# ClosedLoop_Drive_PowerSupply.net
KiCad netlist of a schematic drawn in Altium Designer
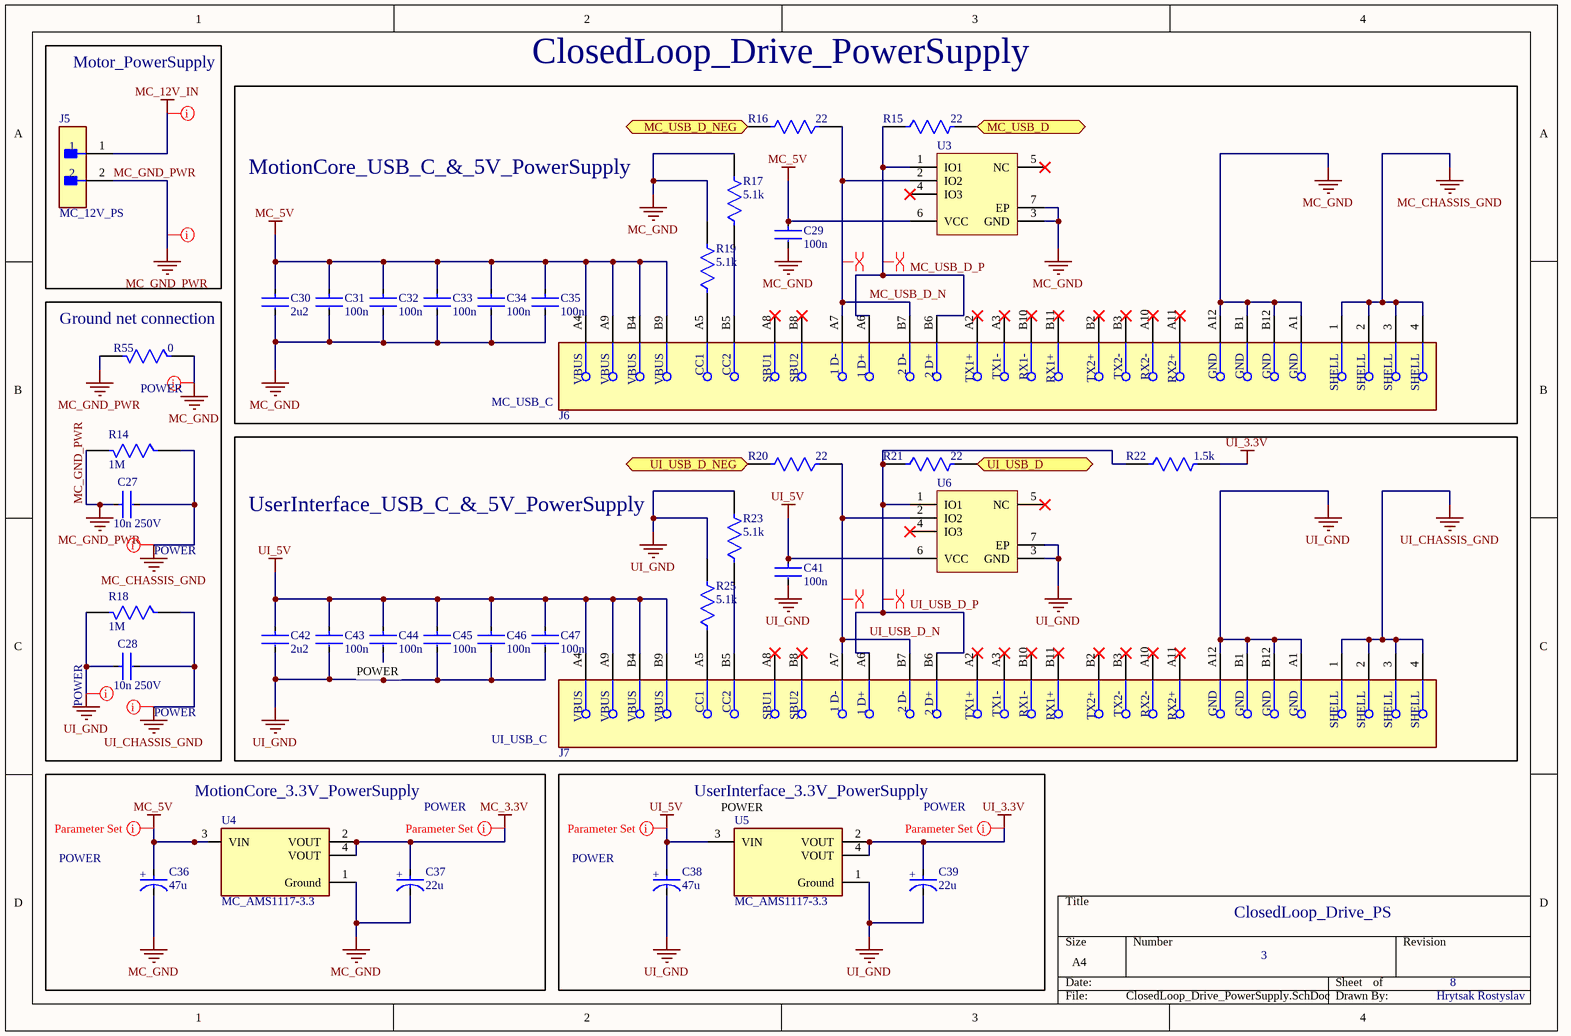
[diagram p0: ClosedLoop_Drive_PowerSupply.SchDoc]

(export (version "E")
  (design (tool "Eeschema 10.0.6"))
  (components
    (comp (ref "C27")
      (value "10n 250V")
      (footprint "FP-0805-L_2_01_0_2-W_1_25-MFG")
      (description "0805")
      (fields (field (name "TOLERANCE") "10%"))
      (libsource (lib "Altium Content Vault") (part "b4654b650e69147ec39a6b967a45e02"))
    )
    (comp (ref "C28")
      (value "10n 250V")
      (footprint "FP-0805-L_2_01_0_2-W_1_25-MFG")
      (description "0805")
      (fields (field (name "TOLERANCE") "10%"))
      (libsource (lib "Altium Content Vault") (part "b4654b650e69147ec39a6b967a45e02"))
    )
    (comp (ref "C29")
      (value "100n")
      (footprint "FP-0805-L_2_01_0_2-W_1_25-MFG")
      (description "0805")
      (fields (field (name "TOLERANCE") "10%"))
      (libsource (lib "Altium Content Vault") (part "b4654b650e69147ec39a6b967a45e02"))
    )
    (comp (ref "C30")
      (value "2u2")
      (footprint "FP-0805-L_2_01_0_2-W_1_25-MFG")
      (description "0805")
      (fields (field (name "TOLERANCE") "10%"))
      (libsource (lib "Altium Content Vault") (part "b4654b650e69147ec39a6b967a45e02"))
    )
    (comp (ref "C31")
      (value "100n")
      (footprint "FP-0805-L_2_01_0_2-W_1_25-MFG")
      (description "0805")
      (fields (field (name "TOLERANCE") "10%"))
      (libsource (lib "Altium Content Vault") (part "b4654b650e69147ec39a6b967a45e02"))
    )
    (comp (ref "C32")
      (value "100n")
      (footprint "FP-0805-L_2_01_0_2-W_1_25-MFG")
      (description "0805")
      (fields (field (name "TOLERANCE") "10%"))
      (libsource (lib "Altium Content Vault") (part "b4654b650e69147ec39a6b967a45e02"))
    )
    (comp (ref "C33")
      (value "100n")
      (footprint "FP-0805-L_2_01_0_2-W_1_25-MFG")
      (description "0805")
      (fields (field (name "TOLERANCE") "10%"))
      (libsource (lib "Altium Content Vault") (part "b4654b650e69147ec39a6b967a45e02"))
    )
    (comp (ref "C34")
      (value "100n")
      (footprint "FP-0805-L_2_01_0_2-W_1_25-MFG")
      (description "0805")
      (fields (field (name "TOLERANCE") "10%"))
      (libsource (lib "Altium Content Vault") (part "b4654b650e69147ec39a6b967a45e02"))
    )
    (comp (ref "C35")
      (value "100n")
      (footprint "FP-0805-L_2_01_0_2-W_1_25-MFG")
      (description "0805")
      (fields (field (name "TOLERANCE") "10%"))
      (libsource (lib "Altium Content Vault") (part "b4654b650e69147ec39a6b967a45e02"))
    )
    (comp (ref "C36")
      (value "47u")
      (footprint "FP-RAD-TH-D_6_3_0_5-L_11-MFG")
      (description "Aluminum Electrolytic Capacitors (Radial Lead Type) AEC-Q200 Qualified 100uF ±20% 25V")
      (fields (field (name "TOLERANCE") "20%"))
      (libsource (lib "Altium Content Vault") (part "203bc49f2ac43e59fd269a8c329ed05"))
    )
    (comp (ref "C37")
      (value "22u")
      (footprint "FP-RAD-TH-D_6_3_0_5-L_11-MFG")
      (description "Aluminum Electrolytic Capacitors (Radial Lead Type) AEC-Q200 Qualified 100uF ±20% 25V")
      (fields (field (name "TOLERANCE") "20%"))
      (libsource (lib "Altium Content Vault") (part "203bc49f2ac43e59fd269a8c329ed05"))
    )
    (comp (ref "C38")
      (value "47u")
      (footprint "FP-RAD-TH-D_6_3_0_5-L_11-MFG")
      (description "Aluminum Electrolytic Capacitors (Radial Lead Type) AEC-Q200 Qualified 100uF ±20% 25V")
      (fields (field (name "TOLERANCE") "20%"))
      (libsource (lib "Altium Content Vault") (part "203bc49f2ac43e59fd269a8c329ed05"))
    )
    (comp (ref "C39")
      (value "22u")
      (footprint "FP-RAD-TH-D_6_3_0_5-L_11-MFG")
      (description "Aluminum Electrolytic Capacitors (Radial Lead Type) AEC-Q200 Qualified 100uF ±20% 25V")
      (fields (field (name "TOLERANCE") "20%"))
      (libsource (lib "Altium Content Vault") (part "203bc49f2ac43e59fd269a8c329ed05"))
    )
    (comp (ref "C41")
      (value "100n")
      (footprint "FP-0805-L_2_01_0_2-W_1_25-MFG")
      (description "0805")
      (fields (field (name "TOLERANCE") "10%"))
      (libsource (lib "Altium Content Vault") (part "b4654b650e69147ec39a6b967a45e02"))
    )
    (comp (ref "C42")
      (value "2u2")
      (footprint "FP-0805-L_2_01_0_2-W_1_25-MFG")
      (description "0805")
      (fields (field (name "TOLERANCE") "10%"))
      (libsource (lib "Altium Content Vault") (part "b4654b650e69147ec39a6b967a45e02"))
    )
    (comp (ref "C43")
      (value "100n")
      (footprint "FP-0805-L_2_01_0_2-W_1_25-MFG")
      (description "0805")
      (fields (field (name "TOLERANCE") "10%"))
      (libsource (lib "Altium Content Vault") (part "b4654b650e69147ec39a6b967a45e02"))
    )
    (comp (ref "C44")
      (value "100n")
      (footprint "FP-0805-L_2_01_0_2-W_1_25-MFG")
      (description "0805")
      (fields (field (name "TOLERANCE") "10%"))
      (libsource (lib "Altium Content Vault") (part "b4654b650e69147ec39a6b967a45e02"))
    )
    (comp (ref "C45")
      (value "100n")
      (footprint "FP-0805-L_2_01_0_2-W_1_25-MFG")
      (description "0805")
      (fields (field (name "TOLERANCE") "10%"))
      (libsource (lib "Altium Content Vault") (part "b4654b650e69147ec39a6b967a45e02"))
    )
    (comp (ref "C46")
      (value "100n")
      (footprint "FP-0805-L_2_01_0_2-W_1_25-MFG")
      (description "0805")
      (fields (field (name "TOLERANCE") "10%"))
      (libsource (lib "Altium Content Vault") (part "b4654b650e69147ec39a6b967a45e02"))
    )
    (comp (ref "C47")
      (value "100n")
      (footprint "FP-0805-L_2_01_0_2-W_1_25-MFG")
      (description "0805")
      (fields (field (name "TOLERANCE") "10%"))
      (libsource (lib "Altium Content Vault") (part "b4654b650e69147ec39a6b967a45e02"))
    )
    (comp (ref "J5")
      (value "MC_12V_PS")
      (footprint "FP-TSW-102-07-F-S-MFG")
      (description "CONN HEADER VERT 2POS 2.54MM")
      (libsource (lib "Altium Content Vault") (part "3bc925449376181038e59eaffc5286c"))
    )
    (comp (ref "J6")
      (value "MC_USB_C")
      (footprint "FP-12401832E402A-MFG")
      (description "CONN RCP USB3.1 TYPEC 24P SMD RA")
      (libsource (lib "Altium Content Vault") (part "50854493bfec571c3c083d899a0df29"))
    )
    (comp (ref "J7")
      (value "UI_USB_C")
      (footprint "FP-12401832E402A-MFG")
      (description "CONN RCP USB3.1 TYPEC 24P SMD RA")
      (libsource (lib "Altium Content Vault") (part "50854493bfec571c3c083d899a0df29"))
    )
    (comp (ref "R14")
      (value "1M")
      (footprint "FP-MCU0805-IPC_A")
      (description "0805")
      (fields (field (name "TOLERANCE") "0.5%"))
      (libsource (lib "Altium Content Vault") (part "1029c3af85768c4190bb7ad29bc67b5"))
    )
    (comp (ref "R15")
      (value "22")
      (footprint "FP-MCU0805-IPC_A")
      (description "0805")
      (fields (field (name "TOLERANCE") "0.5%"))
      (libsource (lib "Altium Content Vault") (part "1029c3af85768c4190bb7ad29bc67b5"))
    )
    (comp (ref "R16")
      (value "22")
      (footprint "FP-MCU0805-IPC_A")
      (description "0805")
      (fields (field (name "TOLERANCE") "0.5%"))
      (libsource (lib "Altium Content Vault") (part "1029c3af85768c4190bb7ad29bc67b5"))
    )
    (comp (ref "R17")
      (value "5.1k")
      (footprint "FP-MCU0805-IPC_A")
      (description "0805")
      (fields (field (name "TOLERANCE") "0.5%"))
      (libsource (lib "Altium Content Vault") (part "1029c3af85768c4190bb7ad29bc67b5"))
    )
    (comp (ref "R18")
      (value "1M")
      (footprint "FP-MCU0805-IPC_A")
      (description "0805")
      (fields (field (name "TOLERANCE") "0.5%"))
      (libsource (lib "Altium Content Vault") (part "1029c3af85768c4190bb7ad29bc67b5"))
    )
    (comp (ref "R19")
      (value "5.1k")
      (footprint "FP-MCU0805-IPC_A")
      (description "0805")
      (fields (field (name "TOLERANCE") "0.5%"))
      (libsource (lib "Altium Content Vault") (part "1029c3af85768c4190bb7ad29bc67b5"))
    )
    (comp (ref "R20")
      (value "22")
      (footprint "FP-MCU0805-IPC_A")
      (description "0805")
      (fields (field (name "TOLERANCE") "0.5%"))
      (libsource (lib "Altium Content Vault") (part "1029c3af85768c4190bb7ad29bc67b5"))
    )
    (comp (ref "R21")
      (value "22")
      (footprint "FP-MCU0805-IPC_A")
      (description "0805")
      (fields (field (name "TOLERANCE") "0.5%"))
      (libsource (lib "Altium Content Vault") (part "1029c3af85768c4190bb7ad29bc67b5"))
    )
    (comp (ref "R22")
      (value "1.5k")
      (footprint "FP-MCU0805-IPC_A")
      (description "0805")
      (fields (field (name "TOLERANCE") "0.5%"))
      (libsource (lib "Altium Content Vault") (part "1029c3af85768c4190bb7ad29bc67b5"))
    )
    (comp (ref "R23")
      (value "5.1k")
      (footprint "FP-MCU0805-IPC_A")
      (description "0805")
      (fields (field (name "TOLERANCE") "0.5%"))
      (libsource (lib "Altium Content Vault") (part "1029c3af85768c4190bb7ad29bc67b5"))
    )
    (comp (ref "R25")
      (value "5.1k")
      (footprint "FP-MCU0805-IPC_A")
      (description "0805")
      (fields (field (name "TOLERANCE") "0.5%"))
      (libsource (lib "Altium Content Vault") (part "1029c3af85768c4190bb7ad29bc67b5"))
    )
    (comp (ref "R55")
      (value "0")
      (footprint "FP-MCU0805-IPC_A")
      (description "0805")
      (fields (field (name "TOLERANCE") "0.5%"))
      (libsource (lib "Altium Content Vault") (part "1029c3af85768c4190bb7ad29bc67b5"))
    )
    (comp (ref "U3")
      (value "~")
      (footprint "DRS0006A_V")
      (fields (field (name "MANUFACTURER") "Texas Instruments") (field (name "PARTNUMBER") "TPD3E001DRSR"))
      (libsource (lib "Altium Content Vault") (part "TI-TPD3E001-SON_DRS-6"))
    )
    (comp (ref "U4")
      (value "MC_AMS1117-3.3")
      (footprint "FP-AMS1117-IPC_C")
      (description "LDO Voltage Regulators 1A, 3.3V")
      (fields
        (field (name "MANUFACTURER PART NUMBER") "AMS1117-3.3")
        (field (name "OCTOPART") "https://octopart.com/ams1117-3.3-advanced+monolithic+systems-25899300")
      )
      (libsource (lib "Altium Content Vault") (part "8bdbb5f8e77002000e30dd2845d0354"))
    )
    (comp (ref "U5")
      (value "MC_AMS1117-3.3")
      (footprint "FP-AMS1117-IPC_C")
      (description "LDO Voltage Regulators 1A, 3.3V")
      (fields
        (field (name "MANUFACTURER PART NUMBER") "AMS1117-3.3")
        (field (name "OCTOPART") "https://octopart.com/ams1117-3.3-advanced+monolithic+systems-25899300")
      )
      (libsource (lib "Altium Content Vault") (part "8bdbb5f8e77002000e30dd2845d0354"))
    )
    (comp (ref "U6")
      (value "~")
      (footprint "DRS0006A_V")
      (fields (field (name "MANUFACTURER") "Texas Instruments") (field (name "PARTNUMBER") "TPD3E001DRSR"))
      (libsource (lib "Altium Content Vault") (part "TI-TPD3E001-SON_DRS-6"))
    )
  )
  (nets
    (net (code "1") (name "/MC_USB_D") (class "Default")
      (node (ref "R15") (pin "2") (pinfunction "2_2") (pintype "passive"))
    )
    (net (code "2") (name "/MC_USB_D_N") (class "Default")
      (node (ref "J6") (pin "A7") (pinfunction "1_D-_A7") (pintype "passive"))
      (node (ref "J6") (pin "B7") (pinfunction "2_D-_B7") (pintype "passive"))
      (node (ref "R16") (pin "1") (pinfunction "1_1") (pintype "passive"))
      (node (ref "U3") (pin "2") (pinfunction "IO2_2") (pintype "passive"))
    )
    (net (code "3") (name "/MC_USB_D_NEG") (class "Default")
      (node (ref "R16") (pin "2") (pinfunction "2_2") (pintype "passive"))
    )
    (net (code "4") (name "/MC_USB_D_P") (class "Default")
      (node (ref "J6") (pin "A6") (pinfunction "1_D+_A6") (pintype "passive"))
      (node (ref "J6") (pin "B6") (pinfunction "2_D+_B6") (pintype "passive"))
      (node (ref "R15") (pin "1") (pinfunction "1_1") (pintype "passive"))
      (node (ref "U3") (pin "1") (pinfunction "IO1_1") (pintype "passive"))
    )
    (net (code "5") (name "/UI_USB_D") (class "Default")
      (node (ref "R21") (pin "2") (pinfunction "2_2") (pintype "passive"))
    )
    (net (code "6") (name "/UI_USB_D_N") (class "Default")
      (node (ref "J7") (pin "A7") (pinfunction "1_D-_A7") (pintype "passive"))
      (node (ref "J7") (pin "B7") (pinfunction "2_D-_B7") (pintype "passive"))
      (node (ref "R20") (pin "1") (pinfunction "1_1") (pintype "passive"))
      (node (ref "U6") (pin "2") (pinfunction "IO2_2") (pintype "passive"))
    )
    (net (code "7") (name "/UI_USB_D_NEG") (class "Default")
      (node (ref "R20") (pin "2") (pinfunction "2_2") (pintype "passive"))
    )
    (net (code "8") (name "/UI_USB_D_P") (class "Default")
      (node (ref "J7") (pin "A6") (pinfunction "1_D+_A6") (pintype "passive"))
      (node (ref "J7") (pin "B6") (pinfunction "2_D+_B6") (pintype "passive"))
      (node (ref "R21") (pin "1") (pinfunction "1_1") (pintype "passive"))
      (node (ref "R22") (pin "1") (pinfunction "1_1") (pintype "passive"))
      (node (ref "U6") (pin "1") (pinfunction "IO1_1") (pintype "passive"))
    )
    (net (code "9") (name "MC_3.3V") (class "Default")
      (node (ref "C37") (pin "2") (pinfunction "A_2") (pintype "passive"))
      (node (ref "U4") (pin "2") (pinfunction "VOUT_2") (pintype "passive"))
      (node (ref "U4") (pin "4") (pinfunction "VOUT_4") (pintype "passive"))
    )
    (net (code "10") (name "MC_5V") (class "Default")
      (node (ref "C29") (pin "1") (pinfunction "1_1") (pintype "passive"))
      (node (ref "C30") (pin "1") (pinfunction "1_1") (pintype "passive"))
      (node (ref "C31") (pin "1") (pinfunction "1_1") (pintype "passive"))
      (node (ref "C32") (pin "1") (pinfunction "1_1") (pintype "passive"))
      (node (ref "C33") (pin "1") (pinfunction "1_1") (pintype "passive"))
      (node (ref "C34") (pin "1") (pinfunction "1_1") (pintype "passive"))
      (node (ref "C35") (pin "1") (pinfunction "1_1") (pintype "passive"))
      (node (ref "C36") (pin "2") (pinfunction "A_2") (pintype "passive"))
      (node (ref "J6") (pin "A4") (pinfunction "VBUS_A4") (pintype "passive"))
      (node (ref "J6") (pin "A9") (pinfunction "VBUS_A9") (pintype "power_in"))
      (node (ref "J6") (pin "B4") (pinfunction "VBUS_B4") (pintype "passive"))
      (node (ref "J6") (pin "B9") (pinfunction "VBUS_B9") (pintype "power_in"))
      (node (ref "U3") (pin "6") (pinfunction "VCC_6") (pintype "power_in"))
      (node (ref "U4") (pin "3") (pinfunction "VIN_3") (pintype "power_in"))
    )
    (net (code "11") (name "MC_12V_IN") (class "Default")
      (node (ref "J5") (pin "1") (pinfunction "1_1") (pintype "passive"))
    )
    (net (code "12") (name "MC_CHASSIS_GND") (class "Default")
      (node (ref "C27") (pin "2") (pinfunction "2_2") (pintype "passive"))
      (node (ref "J6") (pin "1") (pinfunction "SHELL_1") (pintype "power_in"))
      (node (ref "J6") (pin "2") (pinfunction "SHELL_2") (pintype "passive"))
      (node (ref "J6") (pin "3") (pinfunction "SHELL_3") (pintype "passive"))
      (node (ref "J6") (pin "4") (pinfunction "SHELL_4") (pintype "power_in"))
      (node (ref "R14") (pin "1") (pinfunction "1_1") (pintype "passive"))
    )
    (net (code "13") (name "MC_GND") (class "Default")
      (node (ref "C29") (pin "2") (pinfunction "2_2") (pintype "passive"))
      (node (ref "C30") (pin "2") (pinfunction "2_2") (pintype "passive"))
      (node (ref "C31") (pin "2") (pinfunction "2_2") (pintype "passive"))
      (node (ref "C32") (pin "2") (pinfunction "2_2") (pintype "passive"))
      (node (ref "C33") (pin "2") (pinfunction "2_2") (pintype "passive"))
      (node (ref "C34") (pin "2") (pinfunction "2_2") (pintype "passive"))
      (node (ref "C35") (pin "2") (pinfunction "2_2") (pintype "passive"))
      (node (ref "C36") (pin "1") (pinfunction "C_1") (pintype "passive"))
      (node (ref "C37") (pin "1") (pinfunction "C_1") (pintype "passive"))
      (node (ref "J6") (pin "A1") (pinfunction "GND_A1") (pintype "passive"))
      (node (ref "J6") (pin "A12") (pinfunction "GND_A12") (pintype "power_in"))
      (node (ref "J6") (pin "B1") (pinfunction "GND_B1") (pintype "passive"))
      (node (ref "J6") (pin "B12") (pinfunction "GND_B12") (pintype "power_in"))
      (node (ref "R17") (pin "2") (pinfunction "2_2") (pintype "passive"))
      (node (ref "R19") (pin "2") (pinfunction "2_2") (pintype "passive"))
      (node (ref "R55") (pin "1") (pinfunction "1_1") (pintype "passive"))
      (node (ref "U3") (pin "3") (pinfunction "GND_3") (pintype "power_in"))
      (node (ref "U3") (pin "7") (pinfunction "EP_7") (pintype "power_in"))
      (node (ref "U4") (pin "1") (pinfunction "Ground_1") (pintype "power_in"))
    )
    (net (code "14") (name "MC_GND_PWR") (class "Default")
      (node (ref "C27") (pin "1") (pinfunction "1_1") (pintype "passive"))
      (node (ref "J5") (pin "2") (pinfunction "2_2") (pintype "passive"))
      (node (ref "R14") (pin "2") (pinfunction "2_2") (pintype "passive"))
      (node (ref "R55") (pin "2") (pinfunction "2_2") (pintype "passive"))
    )
    (net (code "15") (name "Net-(J6-CC1)") (class "Default")
      (node (ref "J6") (pin "A5") (pinfunction "CC1_A5") (pintype "power_in"))
      (node (ref "R19") (pin "1") (pinfunction "1_1") (pintype "passive"))
    )
    (net (code "16") (name "Net-(J6-CC2)") (class "Default")
      (node (ref "J6") (pin "B5") (pinfunction "CC2_B5") (pintype "power_in"))
      (node (ref "R17") (pin "1") (pinfunction "1_1") (pintype "passive"))
    )
    (net (code "17") (name "Net-(J7-CC1)") (class "Default")
      (node (ref "J7") (pin "A5") (pinfunction "CC1_A5") (pintype "power_in"))
      (node (ref "R25") (pin "1") (pinfunction "1_1") (pintype "passive"))
    )
    (net (code "18") (name "Net-(J7-CC2)") (class "Default")
      (node (ref "J7") (pin "B5") (pinfunction "CC2_B5") (pintype "power_in"))
      (node (ref "R23") (pin "1") (pinfunction "1_1") (pintype "passive"))
    )
    (net (code "19") (name "UI_3.3V") (class "Default")
      (node (ref "C39") (pin "2") (pinfunction "A_2") (pintype "passive"))
      (node (ref "R22") (pin "2") (pinfunction "2_2") (pintype "passive"))
      (node (ref "U5") (pin "2") (pinfunction "VOUT_2") (pintype "passive"))
      (node (ref "U5") (pin "4") (pinfunction "VOUT_4") (pintype "passive"))
    )
    (net (code "20") (name "UI_5V") (class "Default")
      (node (ref "C38") (pin "2") (pinfunction "A_2") (pintype "passive"))
      (node (ref "C41") (pin "1") (pinfunction "1_1") (pintype "passive"))
      (node (ref "C42") (pin "1") (pinfunction "1_1") (pintype "passive"))
      (node (ref "C43") (pin "1") (pinfunction "1_1") (pintype "passive"))
      (node (ref "C44") (pin "1") (pinfunction "1_1") (pintype "passive"))
      (node (ref "C45") (pin "1") (pinfunction "1_1") (pintype "passive"))
      (node (ref "C46") (pin "1") (pinfunction "1_1") (pintype "passive"))
      (node (ref "C47") (pin "1") (pinfunction "1_1") (pintype "passive"))
      (node (ref "J7") (pin "A4") (pinfunction "VBUS_A4") (pintype "passive"))
      (node (ref "J7") (pin "A9") (pinfunction "VBUS_A9") (pintype "power_in"))
      (node (ref "J7") (pin "B4") (pinfunction "VBUS_B4") (pintype "passive"))
      (node (ref "J7") (pin "B9") (pinfunction "VBUS_B9") (pintype "power_in"))
      (node (ref "U5") (pin "3") (pinfunction "VIN_3") (pintype "power_in"))
      (node (ref "U6") (pin "6") (pinfunction "VCC_6") (pintype "power_in"))
    )
    (net (code "21") (name "UI_CHASSIS_GND") (class "Default")
      (node (ref "C28") (pin "2") (pinfunction "2_2") (pintype "passive"))
      (node (ref "J7") (pin "1") (pinfunction "SHELL_1") (pintype "power_in"))
      (node (ref "J7") (pin "2") (pinfunction "SHELL_2") (pintype "passive"))
      (node (ref "J7") (pin "3") (pinfunction "SHELL_3") (pintype "passive"))
      (node (ref "J7") (pin "4") (pinfunction "SHELL_4") (pintype "power_in"))
      (node (ref "R18") (pin "1") (pinfunction "1_1") (pintype "passive"))
    )
    (net (code "22") (name "UI_GND") (class "Default")
      (node (ref "C28") (pin "1") (pinfunction "1_1") (pintype "passive"))
      (node (ref "C38") (pin "1") (pinfunction "C_1") (pintype "passive"))
      (node (ref "C39") (pin "1") (pinfunction "C_1") (pintype "passive"))
      (node (ref "C41") (pin "2") (pinfunction "2_2") (pintype "passive"))
      (node (ref "C42") (pin "2") (pinfunction "2_2") (pintype "passive"))
      (node (ref "C43") (pin "2") (pinfunction "2_2") (pintype "passive"))
      (node (ref "C44") (pin "2") (pinfunction "2_2") (pintype "passive"))
      (node (ref "C45") (pin "2") (pinfunction "2_2") (pintype "passive"))
      (node (ref "C46") (pin "2") (pinfunction "2_2") (pintype "passive"))
      (node (ref "C47") (pin "2") (pinfunction "2_2") (pintype "passive"))
      (node (ref "J7") (pin "A1") (pinfunction "GND_A1") (pintype "passive"))
      (node (ref "J7") (pin "A12") (pinfunction "GND_A12") (pintype "power_in"))
      (node (ref "J7") (pin "B1") (pinfunction "GND_B1") (pintype "passive"))
      (node (ref "J7") (pin "B12") (pinfunction "GND_B12") (pintype "power_in"))
      (node (ref "R18") (pin "2") (pinfunction "2_2") (pintype "passive"))
      (node (ref "R23") (pin "2") (pinfunction "2_2") (pintype "passive"))
      (node (ref "R25") (pin "2") (pinfunction "2_2") (pintype "passive"))
      (node (ref "U5") (pin "1") (pinfunction "Ground_1") (pintype "power_in"))
      (node (ref "U6") (pin "3") (pinfunction "GND_3") (pintype "power_in"))
      (node (ref "U6") (pin "7") (pinfunction "EP_7") (pintype "power_in"))
    )
    (net (code "23") (name "unconnected-(J6-RX1+-PadB11)") (class "Default")
      (node (ref "J6") (pin "B11") (pinfunction "RX1+_B11") (pintype "power_in+no_connect"))
    )
    (net (code "24") (name "unconnected-(J6-RX1--PadB10)") (class "Default")
      (node (ref "J6") (pin "B10") (pinfunction "RX1-_B10") (pintype "power_in+no_connect"))
    )
    (net (code "25") (name "unconnected-(J6-RX2+-PadA11)") (class "Default")
      (node (ref "J6") (pin "A11") (pinfunction "RX2+_A11") (pintype "passive+no_connect"))
    )
    (net (code "26") (name "unconnected-(J6-RX2--PadA10)") (class "Default")
      (node (ref "J6") (pin "A10") (pinfunction "RX2-_A10") (pintype "passive+no_connect"))
    )
    (net (code "27") (name "unconnected-(J6-SBU1-PadA8)") (class "Default")
      (node (ref "J6") (pin "A8") (pinfunction "SBU1_A8") (pintype "power_in+no_connect"))
    )
    (net (code "28") (name "unconnected-(J6-SBU2-PadB8)") (class "Default")
      (node (ref "J6") (pin "B8") (pinfunction "SBU2_B8") (pintype "power_in+no_connect"))
    )
    (net (code "29") (name "unconnected-(J6-TX1+-PadA2)") (class "Default")
      (node (ref "J6") (pin "A2") (pinfunction "TX1+_A2") (pintype "passive+no_connect"))
    )
    (net (code "30") (name "unconnected-(J6-TX1--PadA3)") (class "Default")
      (node (ref "J6") (pin "A3") (pinfunction "TX1-_A3") (pintype "passive+no_connect"))
    )
    (net (code "31") (name "unconnected-(J6-TX2+-PadB2)") (class "Default")
      (node (ref "J6") (pin "B2") (pinfunction "TX2+_B2") (pintype "passive+no_connect"))
    )
    (net (code "32") (name "unconnected-(J6-TX2--PadB3)") (class "Default")
      (node (ref "J6") (pin "B3") (pinfunction "TX2-_B3") (pintype "passive+no_connect"))
    )
    (net (code "33") (name "unconnected-(J7-RX1+-PadB11)") (class "Default")
      (node (ref "J7") (pin "B11") (pinfunction "RX1+_B11") (pintype "power_in+no_connect"))
    )
    (net (code "34") (name "unconnected-(J7-RX1--PadB10)") (class "Default")
      (node (ref "J7") (pin "B10") (pinfunction "RX1-_B10") (pintype "power_in+no_connect"))
    )
    (net (code "35") (name "unconnected-(J7-RX2+-PadA11)") (class "Default")
      (node (ref "J7") (pin "A11") (pinfunction "RX2+_A11") (pintype "passive+no_connect"))
    )
    (net (code "36") (name "unconnected-(J7-RX2--PadA10)") (class "Default")
      (node (ref "J7") (pin "A10") (pinfunction "RX2-_A10") (pintype "passive+no_connect"))
    )
    (net (code "37") (name "unconnected-(J7-SBU1-PadA8)") (class "Default")
      (node (ref "J7") (pin "A8") (pinfunction "SBU1_A8") (pintype "power_in+no_connect"))
    )
    (net (code "38") (name "unconnected-(J7-SBU2-PadB8)") (class "Default")
      (node (ref "J7") (pin "B8") (pinfunction "SBU2_B8") (pintype "power_in+no_connect"))
    )
    (net (code "39") (name "unconnected-(J7-TX1+-PadA2)") (class "Default")
      (node (ref "J7") (pin "A2") (pinfunction "TX1+_A2") (pintype "passive+no_connect"))
    )
    (net (code "40") (name "unconnected-(J7-TX1--PadA3)") (class "Default")
      (node (ref "J7") (pin "A3") (pinfunction "TX1-_A3") (pintype "passive+no_connect"))
    )
    (net (code "41") (name "unconnected-(J7-TX2+-PadB2)") (class "Default")
      (node (ref "J7") (pin "B2") (pinfunction "TX2+_B2") (pintype "passive+no_connect"))
    )
    (net (code "42") (name "unconnected-(J7-TX2--PadB3)") (class "Default")
      (node (ref "J7") (pin "B3") (pinfunction "TX2-_B3") (pintype "passive+no_connect"))
    )
    (net (code "43") (name "unconnected-(U3-IO3-Pad4)") (class "Default")
      (node (ref "U3") (pin "4") (pinfunction "IO3_4") (pintype "passive+no_connect"))
    )
    (net (code "44") (name "unconnected-(U3-NC-Pad5)") (class "Default")
      (node (ref "U3") (pin "5") (pinfunction "NC_5") (pintype "passive+no_connect"))
    )
    (net (code "45") (name "unconnected-(U6-IO3-Pad4)") (class "Default")
      (node (ref "U6") (pin "4") (pinfunction "IO3_4") (pintype "passive+no_connect"))
    )
    (net (code "46") (name "unconnected-(U6-NC-Pad5)") (class "Default")
      (node (ref "U6") (pin "5") (pinfunction "NC_5") (pintype "passive+no_connect"))
    )
  )
)
